# 12v-5v_Buck_Converter.net
KiCad netlist of a schematic drawn in EAGLE
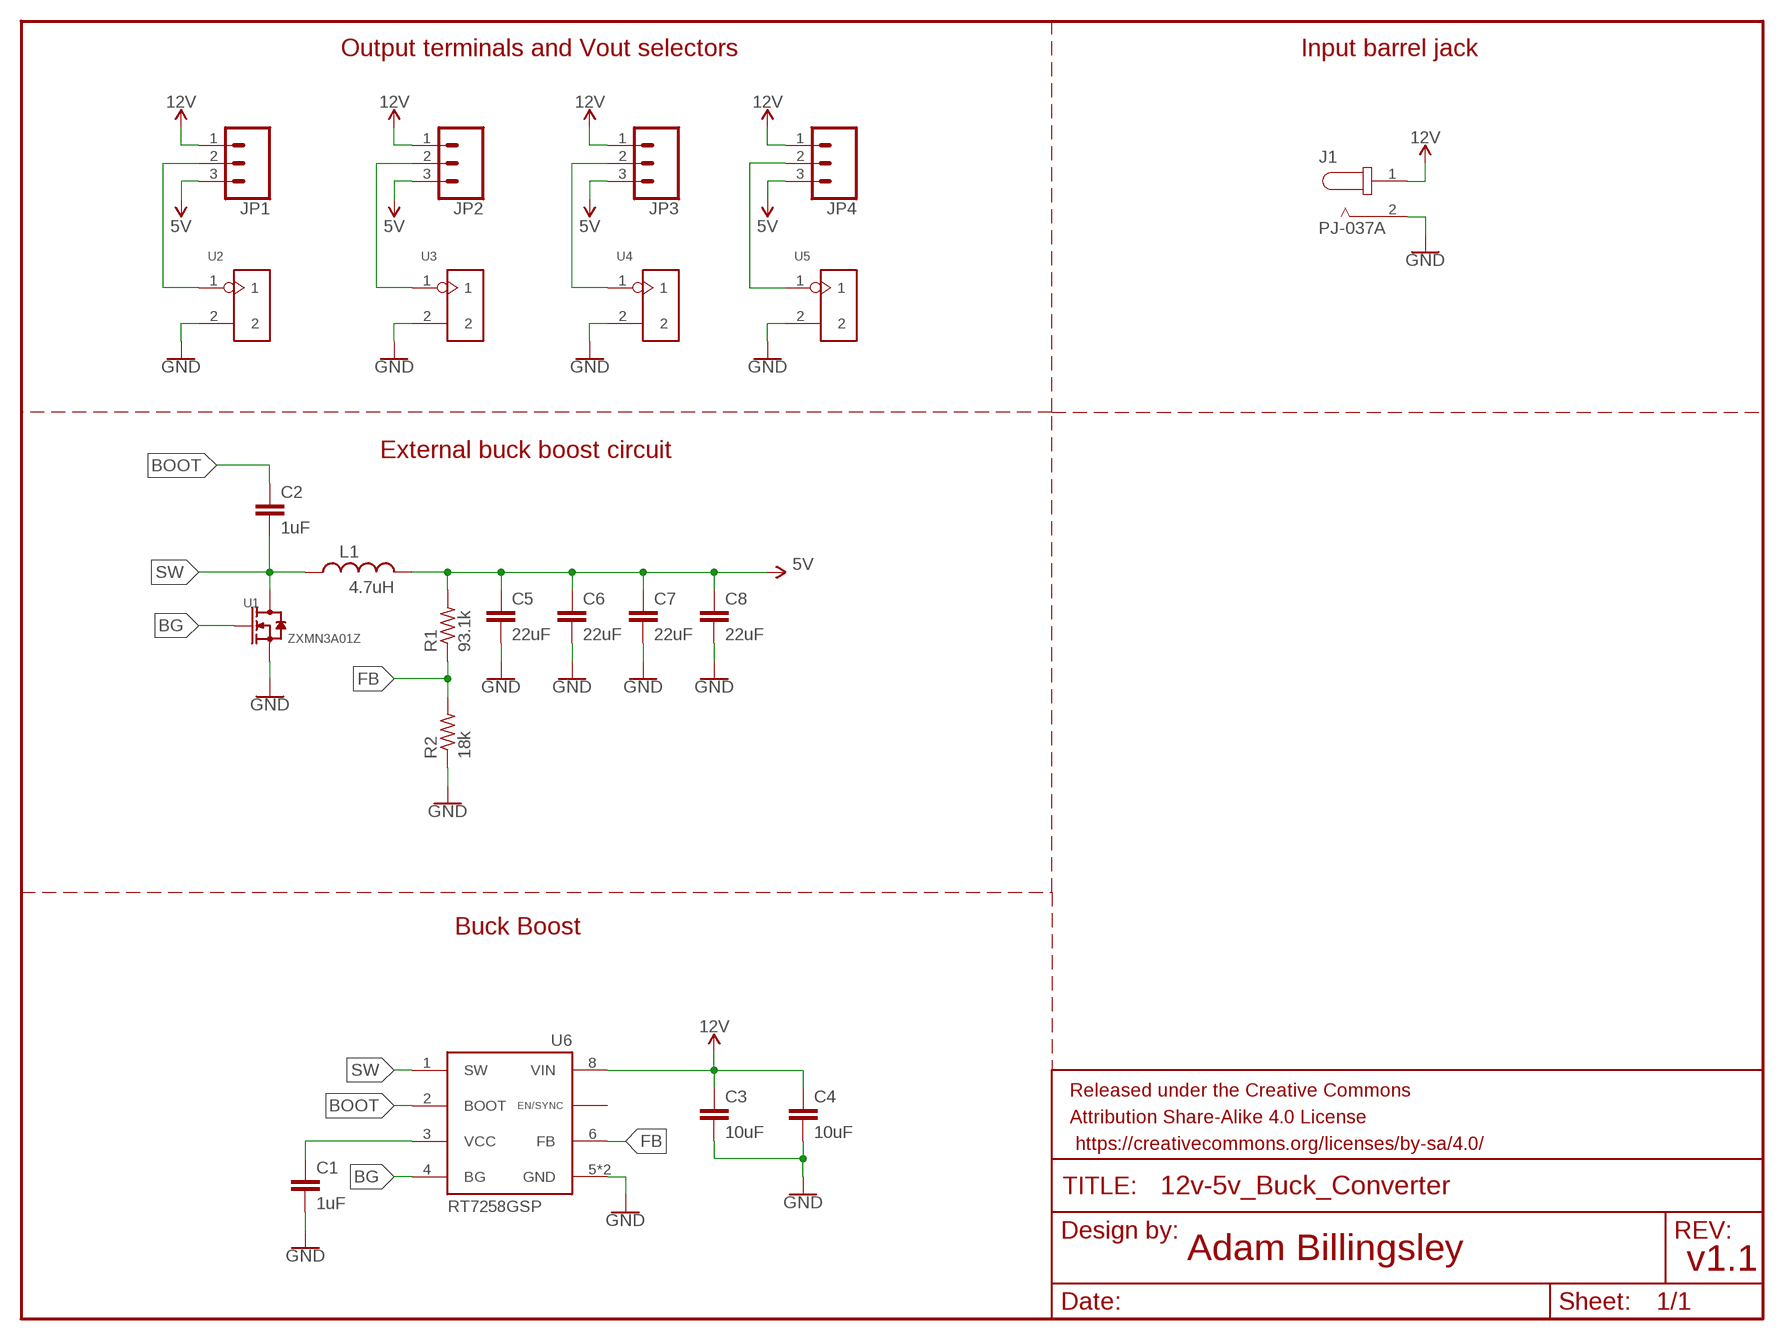
[diagram p0: schematic, sheet 1]

(export (version "E")
  (design (tool "Eeschema 10.0.6"))
  (components
    (comp (ref "C1")
      (value "1uF")
      (footprint "eagle-import:1206-CAPACITOR")
      (libsource (lib "eagle-import") (part "1206_CAPACITOR"))
    )
    (comp (ref "C2")
      (value "1uF")
      (footprint "eagle-import:1206-CAPACITOR")
      (libsource (lib "eagle-import") (part "1206_CAPACITOR"))
    )
    (comp (ref "C3")
      (value "10uF")
      (footprint "eagle-import:1206-CAPACITOR")
      (libsource (lib "eagle-import") (part "1206_CAPACITOR"))
    )
    (comp (ref "C4")
      (value "10uF")
      (footprint "eagle-import:1206-CAPACITOR")
      (libsource (lib "eagle-import") (part "1206_CAPACITOR"))
    )
    (comp (ref "C5")
      (value "22uF")
      (footprint "eagle-import:1210")
      (libsource (lib "eagle-import") (part "1210_CAPACITOR"))
    )
    (comp (ref "C6")
      (value "22uF")
      (footprint "eagle-import:1210")
      (libsource (lib "eagle-import") (part "1210_CAPACITOR"))
    )
    (comp (ref "C7")
      (value "22uF")
      (footprint "eagle-import:1210")
      (libsource (lib "eagle-import") (part "1210_CAPACITOR"))
    )
    (comp (ref "C8")
      (value "22uF")
      (footprint "eagle-import:1210")
      (libsource (lib "eagle-import") (part "1210_CAPACITOR"))
    )
    (comp (ref "FRAME1")
      (value "FRAME-LETTER")
      (footprint "eagle-import:CREATIVE_COMMONS")
      (libsource (lib "eagle-import") (part "FRAME-LETTER"))
    )
    (comp (ref "J1")
      (value "PJ-037A")
      (footprint "eagle-import:CUI_PJ-037A")
      (fields (field (name "MANUFACTURER") "CUI INC"))
      (libsource (lib "eagle-import") (part "PJ-037A"))
    )
    (comp (ref "JP1")
      (value "1X03")
      (footprint "eagle-import:1X03")
      (libsource (lib "eagle-import") (part "1X03"))
    )
    (comp (ref "JP2")
      (value "1X03")
      (footprint "eagle-import:1X03")
      (libsource (lib "eagle-import") (part "1X03"))
    )
    (comp (ref "JP3")
      (value "1X03")
      (footprint "eagle-import:1X03")
      (libsource (lib "eagle-import") (part "1X03"))
    )
    (comp (ref "JP4")
      (value "1X03")
      (footprint "eagle-import:1X03")
      (libsource (lib "eagle-import") (part "1X03"))
    )
    (comp (ref "L1")
      (value "4.7uH")
      (footprint "eagle-import:INDUCTOR-7443330470")
      (libsource (lib "eagle-import") (part "INDUCTOR_7443330470"))
    )
    (comp (ref "R1")
      (value "93.1k")
      (footprint "eagle-import:1206-CAPACITOR")
      (libsource (lib "eagle-import") (part "1206_RESISTOR"))
    )
    (comp (ref "R2")
      (value "18k")
      (footprint "eagle-import:1206-CAPACITOR")
      (libsource (lib "eagle-import") (part "1206_RESISTOR"))
    )
    (comp (ref "U1")
      (value "ZXMN3A01Z")
      (footprint "eagle-import:SI7114DN")
      (libsource (lib "eagle-import") (part "MOSFET-N-SI7114DN"))
    )
    (comp (ref "U2")
      (value "TERMINAL_BLOCK_2P")
      (footprint "eagle-import:H2-5.0-10.5X8.0MM")
      (libsource (lib "eagle-import") (part "TERMINAL_BLOCK_2P"))
    )
    (comp (ref "U3")
      (value "TERMINAL_BLOCK_2P")
      (footprint "eagle-import:H2-5.0-10.5X8.0MM")
      (libsource (lib "eagle-import") (part "TERMINAL_BLOCK_2P"))
    )
    (comp (ref "U4")
      (value "TERMINAL_BLOCK_2P")
      (footprint "eagle-import:H2-5.0-10.5X8.0MM")
      (libsource (lib "eagle-import") (part "TERMINAL_BLOCK_2P"))
    )
    (comp (ref "U5")
      (value "TERMINAL_BLOCK_2P")
      (footprint "eagle-import:H2-5.0-10.5X8.0MM")
      (libsource (lib "eagle-import") (part "TERMINAL_BLOCK_2P"))
    )
    (comp (ref "U6")
      (value "RT7258GSP")
      (footprint "eagle-import:SOP-8E")
      (libsource (lib "eagle-import") (part "RT7258GSP"))
    )
  )
  (nets
    (net (code "1") (name "5V") (class "Default")
      (node (ref "C5") (pin "1") (pinfunction "1_1") (pintype "passive"))
      (node (ref "C6") (pin "1") (pinfunction "1_1") (pintype "passive"))
      (node (ref "C7") (pin "1") (pinfunction "1_1") (pintype "passive"))
      (node (ref "C8") (pin "1") (pinfunction "1_1") (pintype "passive"))
      (node (ref "JP1") (pin "3") (pinfunction "3_3") (pintype "passive"))
      (node (ref "JP2") (pin "3") (pinfunction "3_3") (pintype "passive"))
      (node (ref "JP3") (pin "3") (pinfunction "3_3") (pintype "passive"))
      (node (ref "JP4") (pin "3") (pinfunction "3_3") (pintype "passive"))
      (node (ref "L1") (pin "2") (pinfunction "2_2") (pintype "passive"))
      (node (ref "R1") (pin "2") (pinfunction "2_2") (pintype "passive"))
    )
    (net (code "2") (name "12V") (class "Default")
      (node (ref "C3") (pin "1") (pinfunction "1_1") (pintype "passive"))
      (node (ref "C4") (pin "1") (pinfunction "1_1") (pintype "passive"))
      (node (ref "J1") (pin "1") (pinfunction "1_1") (pintype "passive"))
      (node (ref "JP1") (pin "1") (pinfunction "1_1") (pintype "passive"))
      (node (ref "JP2") (pin "1") (pinfunction "1_1") (pintype "passive"))
      (node (ref "JP3") (pin "1") (pinfunction "1_1") (pintype "passive"))
      (node (ref "JP4") (pin "1") (pinfunction "1_1") (pintype "passive"))
      (node (ref "U6") (pin "8") (pinfunction "VIN_8") (pintype "power_in"))
    )
    (net (code "3") (name "BG") (class "Default")
      (node (ref "U1") (pin "4") (pinfunction "G_4") (pintype "passive"))
      (node (ref "U6") (pin "4") (pinfunction "BG_4") (pintype "output"))
    )
    (net (code "4") (name "BOOT") (class "Default")
      (node (ref "C2") (pin "1") (pinfunction "1_1") (pintype "passive"))
      (node (ref "U6") (pin "2") (pinfunction "BOOT_2") (pintype "bidirectional"))
    )
    (net (code "5") (name "FB") (class "Default")
      (node (ref "R1") (pin "1") (pinfunction "1_1") (pintype "passive"))
      (node (ref "R2") (pin "2") (pinfunction "2_2") (pintype "passive"))
      (node (ref "U6") (pin "6") (pinfunction "FB_6") (pintype "input"))
    )
    (net (code "6") (name "GND") (class "Default")
      (node (ref "C1") (pin "2") (pinfunction "2_2") (pintype "passive"))
      (node (ref "C3") (pin "2") (pinfunction "2_2") (pintype "passive"))
      (node (ref "C4") (pin "2") (pinfunction "2_2") (pintype "passive"))
      (node (ref "C5") (pin "2") (pinfunction "2_2") (pintype "passive"))
      (node (ref "C6") (pin "2") (pinfunction "2_2") (pintype "passive"))
      (node (ref "C7") (pin "2") (pinfunction "2_2") (pintype "passive"))
      (node (ref "C8") (pin "2") (pinfunction "2_2") (pintype "passive"))
      (node (ref "J1") (pin "2") (pinfunction "2_2") (pintype "passive"))
      (node (ref "R2") (pin "1") (pinfunction "1_1") (pintype "passive"))
      (node (ref "U1") (pin "1") (pinfunction "S_1") (pintype "passive"))
      (node (ref "U1") (pin "2") (pinfunction "S_2") (pintype "passive"))
      (node (ref "U1") (pin "3") (pinfunction "S_3") (pintype "passive"))
      (node (ref "U2") (pin "2") (pinfunction "2_2") (pintype "bidirectional"))
      (node (ref "U3") (pin "2") (pinfunction "2_2") (pintype "bidirectional"))
      (node (ref "U4") (pin "2") (pinfunction "2_2") (pintype "bidirectional"))
      (node (ref "U5") (pin "2") (pinfunction "2_2") (pintype "bidirectional"))
      (node (ref "U6") (pin "5") (pinfunction "GND_5") (pintype "power_in"))
      (node (ref "U6") (pin "9") (pinfunction "GND_9") (pintype "power_in"))
    )
    (net (code "7") (name "Net-(JP1-Pad2)") (class "Default")
      (node (ref "JP1") (pin "2") (pinfunction "2_2") (pintype "passive"))
      (node (ref "U2") (pin "1") (pinfunction "1_1") (pintype "bidirectional"))
    )
    (net (code "8") (name "Net-(JP2-Pad2)") (class "Default")
      (node (ref "JP2") (pin "2") (pinfunction "2_2") (pintype "passive"))
      (node (ref "U3") (pin "1") (pinfunction "1_1") (pintype "bidirectional"))
    )
    (net (code "9") (name "Net-(JP3-Pad2)") (class "Default")
      (node (ref "JP3") (pin "2") (pinfunction "2_2") (pintype "passive"))
      (node (ref "U4") (pin "1") (pinfunction "1_1") (pintype "bidirectional"))
    )
    (net (code "10") (name "Net-(JP4-Pad2)") (class "Default")
      (node (ref "JP4") (pin "2") (pinfunction "2_2") (pintype "passive"))
      (node (ref "U5") (pin "1") (pinfunction "1_1") (pintype "bidirectional"))
    )
    (net (code "11") (name "Net-(U6-VCC)") (class "Default")
      (node (ref "C1") (pin "1") (pinfunction "1_1") (pintype "passive"))
      (node (ref "U6") (pin "3") (pinfunction "VCC_3") (pintype "power_in"))
    )
    (net (code "12") (name "SW") (class "Default")
      (node (ref "C2") (pin "2") (pinfunction "2_2") (pintype "passive"))
      (node (ref "L1") (pin "1") (pinfunction "1_1") (pintype "passive"))
      (node (ref "U1") (pin "5") (pinfunction "D_5") (pintype "passive"))
      (node (ref "U1") (pin "6") (pinfunction "D_6") (pintype "passive"))
      (node (ref "U1") (pin "7") (pinfunction "D_7") (pintype "passive"))
      (node (ref "U1") (pin "8") (pinfunction "D_8") (pintype "passive"))
      (node (ref "U1") (pin "9") (pinfunction "D_9") (pintype "passive"))
      (node (ref "U6") (pin "1") (pinfunction "SW_1") (pintype "bidirectional"))
    )
    (net (code "13") (name "unconnected-(U6-EN{slash}SYNC-Pad7)") (class "Default")
      (node (ref "U6") (pin "7") (pinfunction "EN/SYNC_7") (pintype "input"))
    )
  )
)
